# node_kitchen.net
KiCad netlist of a schematic drawn in Altium Designer
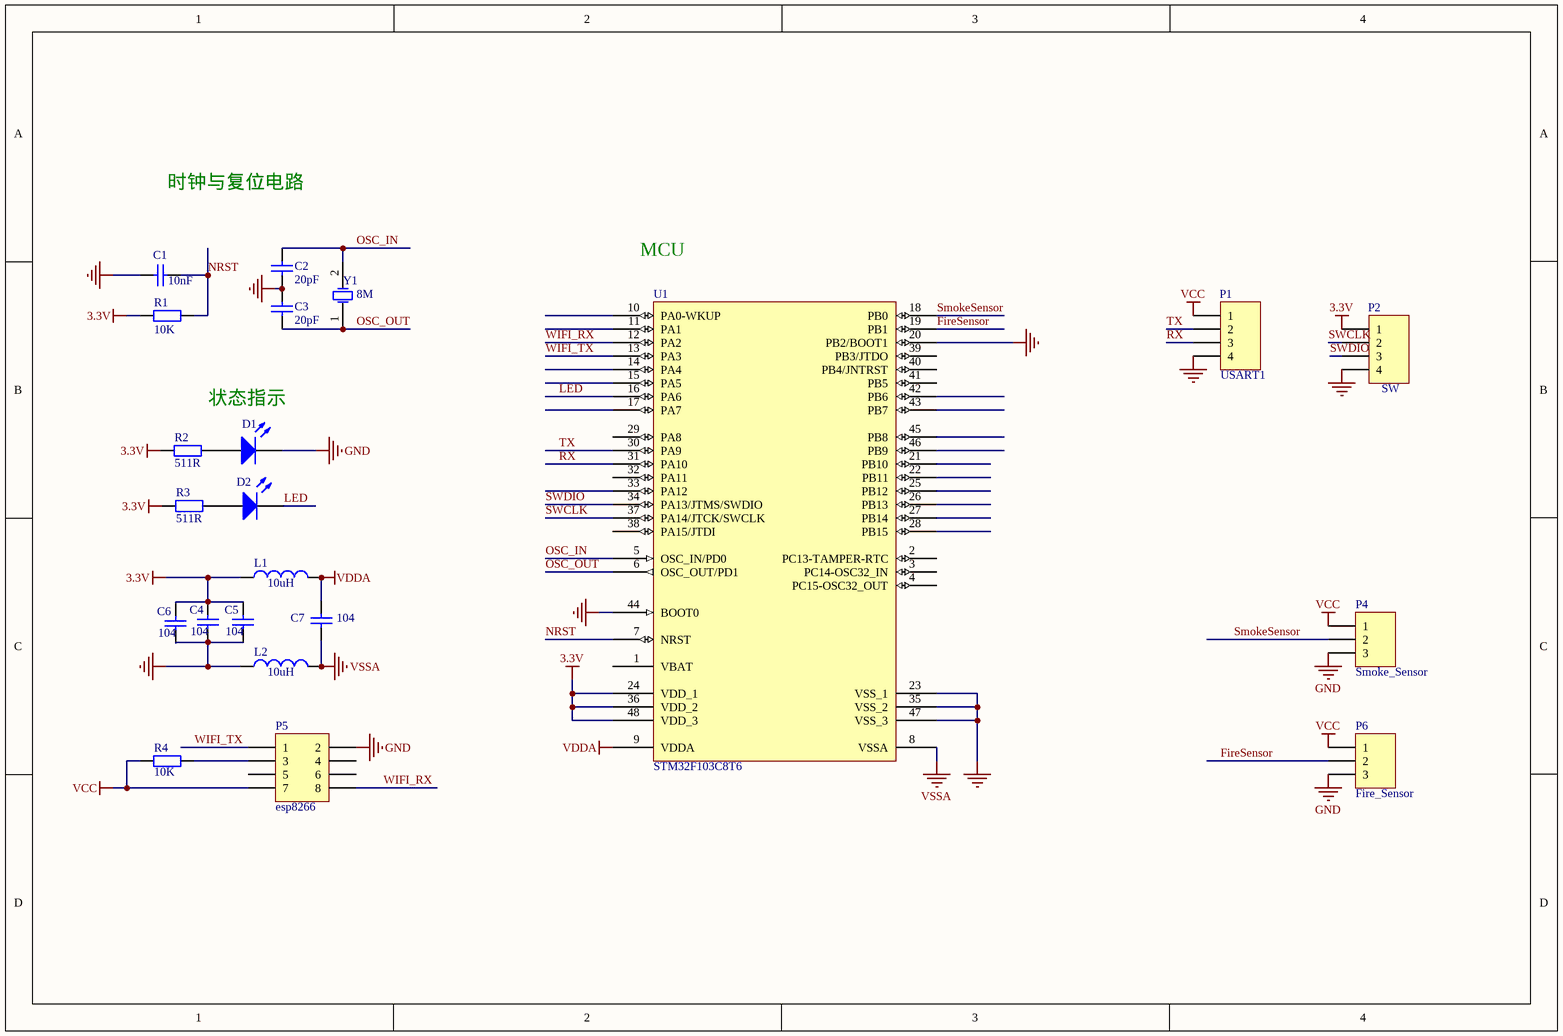
[diagram p0: node_kitchen.SchDoc]

(export (version "E")
  (design (tool "Eeschema 10.0.6"))
  (components
    (comp (ref "C1")
      (value "10nF")
      (footprint "0603-N-CAP")
      (description "Capacitor")
      (fields (field (name "Comment") "Cap") (field (name "PUBLISHER") "Altium Limited"))
      (libsource (lib "Miscellaneous Devices") (part "Cap"))
    )
    (comp (ref "C2")
      (value "20pF")
      (footprint "0603-N-CAP")
      (description "Capacitor")
      (fields (field (name "Comment") "Cap") (field (name "PUBLISHER") "Altium Limited"))
      (libsource (lib "Miscellaneous Devices") (part "Cap"))
    )
    (comp (ref "C3")
      (value "20pF")
      (footprint "0603-N-CAP")
      (description "Capacitor")
      (fields (field (name "Comment") "Cap") (field (name "PUBLISHER") "Altium Limited"))
      (libsource (lib "Miscellaneous Devices") (part "Cap"))
    )
    (comp (ref "C4")
      (value "104")
      (footprint "0603-N-CAP")
      (description "Capacitor")
      (fields (field (name "Comment") "Cap") (field (name "PUBLISHER") "Altium Limited"))
      (libsource (lib "Miscellaneous Devices") (part "Cap"))
    )
    (comp (ref "C5")
      (value "104")
      (footprint "0603-N-CAP")
      (description "Capacitor")
      (fields (field (name "Comment") "Cap") (field (name "PUBLISHER") "Altium Limited"))
      (libsource (lib "Miscellaneous Devices") (part "Cap"))
    )
    (comp (ref "C6")
      (value "104")
      (footprint "0603-N-CAP")
      (description "Capacitor")
      (fields (field (name "Comment") "Cap") (field (name "PUBLISHER") "Altium Limited"))
      (libsource (lib "Miscellaneous Devices") (part "Cap"))
    )
    (comp (ref "C7")
      (value "104")
      (footprint "0603-N-CAP")
      (description "Capacitor")
      (fields (field (name "Comment") "Cap") (field (name "PUBLISHER") "Altium Limited"))
      (libsource (lib "Miscellaneous Devices") (part "Cap"))
    )
    (comp (ref "D1")
      (value "D2")
      (footprint "0603-N - LED-GRREN")
      (description "Typical BLUE SiC LED")
      (fields (field (name "PUBLISHER") "Altium Limited"))
      (libsource (lib "Miscellaneous Devices") (part "LED3"))
    )
    (comp (ref "D2")
      (value "D2")
      (footprint "0603-N - LED-RED")
      (description "Typical BLUE SiC LED")
      (fields (field (name "PUBLISHER") "Altium Limited"))
      (libsource (lib "Miscellaneous Devices") (part "LED3"))
    )
    (comp (ref "L1")
      (value "10uH")
      (footprint "0603-N - res")
      (description "Inductor")
      (fields (field (name "PUBLISHER") "Altium Limited"))
      (libsource (lib "Miscellaneous Devices") (part "Inductor"))
    )
    (comp (ref "L2")
      (value "10uH")
      (footprint "0603-N - res")
      (description "Inductor")
      (fields (field (name "PUBLISHER") "Altium Limited"))
      (libsource (lib "Miscellaneous Devices") (part "Inductor"))
    )
    (comp (ref "P1")
      (value "USART1")
      (footprint "ZH1.5MM_4P")
      (description "Header, 4-Pin, Right Angle")
      (fields (field (name "PUBLISHER") "Altium Limited"))
      (libsource (lib "Miscellaneous Connectors") (part "Header 4H"))
    )
    (comp (ref "P2")
      (value "SW")
      (footprint "ZH1.5MM_4P")
      (description "Header, 4-Pin, Right Angle")
      (fields (field (name "PUBLISHER") "Altium Limited"))
      (libsource (lib "Miscellaneous Connectors") (part "Header 4H"))
    )
    (comp (ref "P4")
      (value "Smoke_Sensor")
      (footprint "HDR1X3")
      (description "Header, 3-Pin")
      (fields (field (name "PUBLISHER") "Altium Limited"))
      (libsource (lib "Miscellaneous Connectors") (part "Header 3"))
    )
    (comp (ref "P5")
      (value "esp8266")
      (footprint "HDR2X4")
      (description "Header, 4-Pin, Dual row")
      (fields (field (name "PUBLISHER") "Altium Limited"))
      (libsource (lib "Miscellaneous Connectors") (part "Header 4X2"))
    )
    (comp (ref "P6")
      (value "Fire_Sensor")
      (footprint "HDR1X3")
      (description "Header, 3-Pin")
      (fields (field (name "PUBLISHER") "Altium Limited"))
      (libsource (lib "Miscellaneous Connectors") (part "Header 3"))
    )
    (comp (ref "R1")
      (value "10K")
      (footprint "0603-N - res")
      (description "Resistor")
      (fields (field (name "Comment") "Res2") (field (name "PUBLISHER") "Altium Limited"))
      (libsource (lib "Miscellaneous Devices") (part "Res2"))
    )
    (comp (ref "R2")
      (value "511R")
      (footprint "0603-N - res")
      (description "Resistor")
      (fields (field (name "Comment") "Res2") (field (name "PUBLISHER") "Altium Limited"))
      (libsource (lib "Miscellaneous Devices") (part "Res2"))
    )
    (comp (ref "R3")
      (value "511R")
      (footprint "0603-N - res")
      (description "Resistor")
      (fields (field (name "Comment") "Res2") (field (name "PUBLISHER") "Altium Limited"))
      (libsource (lib "Miscellaneous Devices") (part "Res2"))
    )
    (comp (ref "R4")
      (value "10K")
      (footprint "0603-N - res")
      (description "Resistor")
      (fields (field (name "Comment") "Res2") (field (name "PUBLISHER") "Altium Limited"))
      (libsource (lib "") (part "Res2_1"))
    )
    (comp (ref "U1")
      (value "STM32F103C8T6")
      (footprint "LQFP48_N")
      (description "STM32 ARM-based 32-bit MCU with 64 Kbytes Flash, 48-pin LQFP, Industrial Temperature")
      (fields (field (name "PUBLISHER") "Altium Limited"))
      (libsource (lib "ST Microcontroller 32-Bit STM32") (part "STM32F103C8T6"))
    )
    (comp (ref "Y1")
      (value "8M")
      (footprint "5032_")
      (description "Crystal Oscillator")
      (fields (field (name "PUBLISHER") "Altium Limited"))
      (libsource (lib "Miscellaneous Devices") (part "XTAL"))
    )
  )
  (nets
    (net (code "1") (name "/FireSensor") (class "Default")
      (node (ref "P6") (pin "2") (pinfunction "2_2") (pintype "passive"))
      (node (ref "U1") (pin "19") (pinfunction "PB1_19") (pintype "bidirectional"))
    )
    (net (code "2") (name "/LED") (class "Default")
      (node (ref "D2") (pin "2") (pinfunction "K_2") (pintype "passive"))
      (node (ref "U1") (pin "16") (pinfunction "PA6_16") (pintype "bidirectional"))
    )
    (net (code "3") (name "/NRST") (class "Default")
      (node (ref "C1") (pin "2") (pinfunction "2_2") (pintype "passive"))
      (node (ref "R1") (pin "2") (pinfunction "2_2") (pintype "passive"))
      (node (ref "U1") (pin "7") (pinfunction "NRST_7") (pintype "bidirectional"))
    )
    (net (code "4") (name "/OSC_IN") (class "Default")
      (node (ref "C2") (pin "2") (pinfunction "2_2") (pintype "passive"))
      (node (ref "U1") (pin "5") (pinfunction "OSC_IN/PD0_5") (pintype "input"))
      (node (ref "Y1") (pin "2") (pinfunction "OSC2_2") (pintype "passive"))
    )
    (net (code "5") (name "/OSC_OUT") (class "Default")
      (node (ref "C3") (pin "1") (pinfunction "1_1") (pintype "passive"))
      (node (ref "U1") (pin "6") (pinfunction "OSC_OUT/PD1_6") (pintype "output"))
      (node (ref "Y1") (pin "1") (pinfunction "OSC1_1") (pintype "passive"))
    )
    (net (code "6") (name "/RX") (class "Default")
      (node (ref "P1") (pin "3") (pinfunction "3_3") (pintype "passive"))
      (node (ref "U1") (pin "31") (pinfunction "PA10_31") (pintype "bidirectional"))
    )
    (net (code "7") (name "/SWCLK") (class "Default")
      (node (ref "P2") (pin "2") (pinfunction "2_2") (pintype "passive"))
      (node (ref "U1") (pin "37") (pinfunction "PA14/JTCK/SWCLK_37") (pintype "bidirectional"))
    )
    (net (code "8") (name "/SWDIO") (class "Default")
      (node (ref "P2") (pin "3") (pinfunction "3_3") (pintype "passive"))
      (node (ref "U1") (pin "34") (pinfunction "PA13/JTMS/SWDIO_34") (pintype "bidirectional"))
    )
    (net (code "9") (name "/SmokeSensor") (class "Default")
      (node (ref "P4") (pin "2") (pinfunction "2_2") (pintype "passive"))
      (node (ref "U1") (pin "18") (pinfunction "PB0_18") (pintype "bidirectional"))
    )
    (net (code "10") (name "/TX") (class "Default")
      (node (ref "P1") (pin "2") (pinfunction "2_2") (pintype "passive"))
      (node (ref "U1") (pin "30") (pinfunction "PA9_30") (pintype "bidirectional"))
    )
    (net (code "11") (name "/WIFI_RX") (class "Default")
      (node (ref "P5") (pin "8") (pinfunction "8_8") (pintype "passive"))
      (node (ref "U1") (pin "12") (pinfunction "PA2_12") (pintype "bidirectional"))
    )
    (net (code "12") (name "/WIFI_TX") (class "Default")
      (node (ref "P5") (pin "1") (pinfunction "1_1") (pintype "passive"))
      (node (ref "U1") (pin "13") (pinfunction "PA3_13") (pintype "bidirectional"))
    )
    (net (code "13") (name "3.3V") (class "Default")
      (node (ref "C4") (pin "2") (pinfunction "2_2") (pintype "passive"))
      (node (ref "C5") (pin "2") (pinfunction "2_2") (pintype "passive"))
      (node (ref "C6") (pin "2") (pinfunction "2_2") (pintype "passive"))
      (node (ref "L1") (pin "1") (pinfunction "1_1") (pintype "passive"))
      (node (ref "P2") (pin "1") (pinfunction "1_1") (pintype "passive"))
      (node (ref "R1") (pin "1") (pinfunction "1_1") (pintype "passive"))
      (node (ref "R2") (pin "1") (pinfunction "1_1") (pintype "passive"))
      (node (ref "R3") (pin "1") (pinfunction "1_1") (pintype "passive"))
      (node (ref "U1") (pin "24") (pinfunction "VDD_1_24") (pintype "power_in"))
      (node (ref "U1") (pin "36") (pinfunction "VDD_2_36") (pintype "power_in"))
      (node (ref "U1") (pin "48") (pinfunction "VDD_3_48") (pintype "power_in"))
    )
    (net (code "14") (name "GND") (class "Default")
      (node (ref "C1") (pin "1") (pinfunction "1_1") (pintype "passive"))
      (node (ref "C2") (pin "1") (pinfunction "1_1") (pintype "passive"))
      (node (ref "C3") (pin "2") (pinfunction "2_2") (pintype "passive"))
      (node (ref "C4") (pin "1") (pinfunction "1_1") (pintype "passive"))
      (node (ref "C5") (pin "1") (pinfunction "1_1") (pintype "passive"))
      (node (ref "C6") (pin "1") (pinfunction "1_1") (pintype "passive"))
      (node (ref "D1") (pin "2") (pinfunction "K_2") (pintype "passive"))
      (node (ref "L2") (pin "1") (pinfunction "1_1") (pintype "passive"))
      (node (ref "P1") (pin "4") (pinfunction "4_4") (pintype "passive"))
      (node (ref "P2") (pin "4") (pinfunction "4_4") (pintype "passive"))
      (node (ref "P4") (pin "3") (pinfunction "3_3") (pintype "passive"))
      (node (ref "P5") (pin "2") (pinfunction "2_2") (pintype "passive"))
      (node (ref "P6") (pin "3") (pinfunction "3_3") (pintype "passive"))
      (node (ref "U1") (pin "20") (pinfunction "PB2/BOOT1_20") (pintype "bidirectional"))
      (node (ref "U1") (pin "23") (pinfunction "VSS_1_23") (pintype "power_in"))
      (node (ref "U1") (pin "35") (pinfunction "VSS_2_35") (pintype "power_in"))
      (node (ref "U1") (pin "44") (pinfunction "BOOT0_44") (pintype "input"))
      (node (ref "U1") (pin "47") (pinfunction "VSS_3_47") (pintype "power_in"))
    )
    (net (code "15") (name "Net-(D1-A)") (class "Default")
      (node (ref "D1") (pin "1") (pinfunction "A_1") (pintype "passive"))
      (node (ref "R2") (pin "2") (pinfunction "2_2") (pintype "passive"))
    )
    (net (code "16") (name "Net-(D2-A)") (class "Default")
      (node (ref "D2") (pin "1") (pinfunction "A_1") (pintype "passive"))
      (node (ref "R3") (pin "2") (pinfunction "2_2") (pintype "passive"))
    )
    (net (code "17") (name "Net-(P5-Pad3)") (class "Default")
      (node (ref "P5") (pin "3") (pinfunction "3_3") (pintype "passive"))
      (node (ref "R4") (pin "1") (pinfunction "1_1") (pintype "passive"))
    )
    (net (code "18") (name "VCC") (class "Default")
      (node (ref "P1") (pin "1") (pinfunction "1_1") (pintype "passive"))
      (node (ref "P4") (pin "1") (pinfunction "1_1") (pintype "passive"))
      (node (ref "P5") (pin "7") (pinfunction "7_7") (pintype "passive"))
      (node (ref "P6") (pin "1") (pinfunction "1_1") (pintype "passive"))
      (node (ref "R4") (pin "2") (pinfunction "2_2") (pintype "passive"))
    )
    (net (code "19") (name "VDDA") (class "Default")
      (node (ref "C7") (pin "2") (pinfunction "2_2") (pintype "passive"))
      (node (ref "L1") (pin "2") (pinfunction "2_2") (pintype "passive"))
      (node (ref "U1") (pin "9") (pinfunction "VDDA_9") (pintype "power_in"))
    )
    (net (code "20") (name "VSSA") (class "Default")
      (node (ref "C7") (pin "1") (pinfunction "1_1") (pintype "passive"))
      (node (ref "L2") (pin "2") (pinfunction "2_2") (pintype "passive"))
      (node (ref "U1") (pin "8") (pinfunction "VSSA_8") (pintype "power_in"))
    )
    (net (code "21") (name "unconnected-(P5-Pad4)") (class "Default")
      (node (ref "P5") (pin "4") (pinfunction "4_4") (pintype "passive"))
    )
    (net (code "22") (name "unconnected-(P5-Pad5)") (class "Default")
      (node (ref "P5") (pin "5") (pinfunction "5_5") (pintype "passive"))
    )
    (net (code "23") (name "unconnected-(P5-Pad6)") (class "Default")
      (node (ref "P5") (pin "6") (pinfunction "6_6") (pintype "passive"))
    )
    (net (code "24") (name "unconnected-(U1-PA0-WKUP-Pad10)") (class "Default")
      (node (ref "U1") (pin "10") (pinfunction "PA0-WKUP_10") (pintype "bidirectional"))
    )
    (net (code "25") (name "unconnected-(U1-PA1-Pad11)") (class "Default")
      (node (ref "U1") (pin "11") (pinfunction "PA1_11") (pintype "bidirectional"))
    )
    (net (code "26") (name "unconnected-(U1-PA4-Pad14)") (class "Default")
      (node (ref "U1") (pin "14") (pinfunction "PA4_14") (pintype "bidirectional"))
    )
    (net (code "27") (name "unconnected-(U1-PA5-Pad15)") (class "Default")
      (node (ref "U1") (pin "15") (pinfunction "PA5_15") (pintype "bidirectional"))
    )
    (net (code "28") (name "unconnected-(U1-PA7-Pad17)") (class "Default")
      (node (ref "U1") (pin "17") (pinfunction "PA7_17") (pintype "bidirectional"))
    )
    (net (code "29") (name "unconnected-(U1-PA8-Pad29)") (class "Default")
      (node (ref "U1") (pin "29") (pinfunction "PA8_29") (pintype "bidirectional"))
    )
    (net (code "30") (name "unconnected-(U1-PA11-Pad32)") (class "Default")
      (node (ref "U1") (pin "32") (pinfunction "PA11_32") (pintype "bidirectional"))
    )
    (net (code "31") (name "unconnected-(U1-PA12-Pad33)") (class "Default")
      (node (ref "U1") (pin "33") (pinfunction "PA12_33") (pintype "bidirectional"))
    )
    (net (code "32") (name "unconnected-(U1-PA15{slash}JTDI-Pad38)") (class "Default")
      (node (ref "U1") (pin "38") (pinfunction "PA15/JTDI_38") (pintype "bidirectional"))
    )
    (net (code "33") (name "unconnected-(U1-PB3{slash}JTDO-Pad39)") (class "Default")
      (node (ref "U1") (pin "39") (pinfunction "PB3/JTDO_39") (pintype "bidirectional"))
    )
    (net (code "34") (name "unconnected-(U1-PB4{slash}JNTRST-Pad40)") (class "Default")
      (node (ref "U1") (pin "40") (pinfunction "PB4/JNTRST_40") (pintype "bidirectional"))
    )
    (net (code "35") (name "unconnected-(U1-PB5-Pad41)") (class "Default")
      (node (ref "U1") (pin "41") (pinfunction "PB5_41") (pintype "bidirectional"))
    )
    (net (code "36") (name "unconnected-(U1-PB6-Pad42)") (class "Default")
      (node (ref "U1") (pin "42") (pinfunction "PB6_42") (pintype "bidirectional"))
    )
    (net (code "37") (name "unconnected-(U1-PB7-Pad43)") (class "Default")
      (node (ref "U1") (pin "43") (pinfunction "PB7_43") (pintype "bidirectional"))
    )
    (net (code "38") (name "unconnected-(U1-PB8-Pad45)") (class "Default")
      (node (ref "U1") (pin "45") (pinfunction "PB8_45") (pintype "bidirectional"))
    )
    (net (code "39") (name "unconnected-(U1-PB9-Pad46)") (class "Default")
      (node (ref "U1") (pin "46") (pinfunction "PB9_46") (pintype "bidirectional"))
    )
    (net (code "40") (name "unconnected-(U1-PB10-Pad21)") (class "Default")
      (node (ref "U1") (pin "21") (pinfunction "PB10_21") (pintype "bidirectional"))
    )
    (net (code "41") (name "unconnected-(U1-PB11-Pad22)") (class "Default")
      (node (ref "U1") (pin "22") (pinfunction "PB11_22") (pintype "bidirectional"))
    )
    (net (code "42") (name "unconnected-(U1-PB12-Pad25)") (class "Default")
      (node (ref "U1") (pin "25") (pinfunction "PB12_25") (pintype "bidirectional"))
    )
    (net (code "43") (name "unconnected-(U1-PB13-Pad26)") (class "Default")
      (node (ref "U1") (pin "26") (pinfunction "PB13_26") (pintype "bidirectional"))
    )
    (net (code "44") (name "unconnected-(U1-PB14-Pad27)") (class "Default")
      (node (ref "U1") (pin "27") (pinfunction "PB14_27") (pintype "bidirectional"))
    )
    (net (code "45") (name "unconnected-(U1-PB15-Pad28)") (class "Default")
      (node (ref "U1") (pin "28") (pinfunction "PB15_28") (pintype "bidirectional"))
    )
    (net (code "46") (name "unconnected-(U1-PC13-TAMPER-RTC-Pad2)") (class "Default")
      (node (ref "U1") (pin "2") (pinfunction "PC13-TAMPER-RTC_2") (pintype "bidirectional"))
    )
    (net (code "47") (name "unconnected-(U1-PC14-OSC32_IN-Pad3)") (class "Default")
      (node (ref "U1") (pin "3") (pinfunction "PC14-OSC32_IN_3") (pintype "bidirectional"))
    )
    (net (code "48") (name "unconnected-(U1-PC15-OSC32_OUT-Pad4)") (class "Default")
      (node (ref "U1") (pin "4") (pinfunction "PC15-OSC32_OUT_4") (pintype "bidirectional"))
    )
    (net (code "49") (name "unconnected-(U1-VBAT-Pad1)") (class "Default")
      (node (ref "U1") (pin "1") (pinfunction "VBAT_1") (pintype "power_in"))
    )
  )
)
